# USBTypeConverter.net
KiCad netlist of a schematic drawn in EAGLE
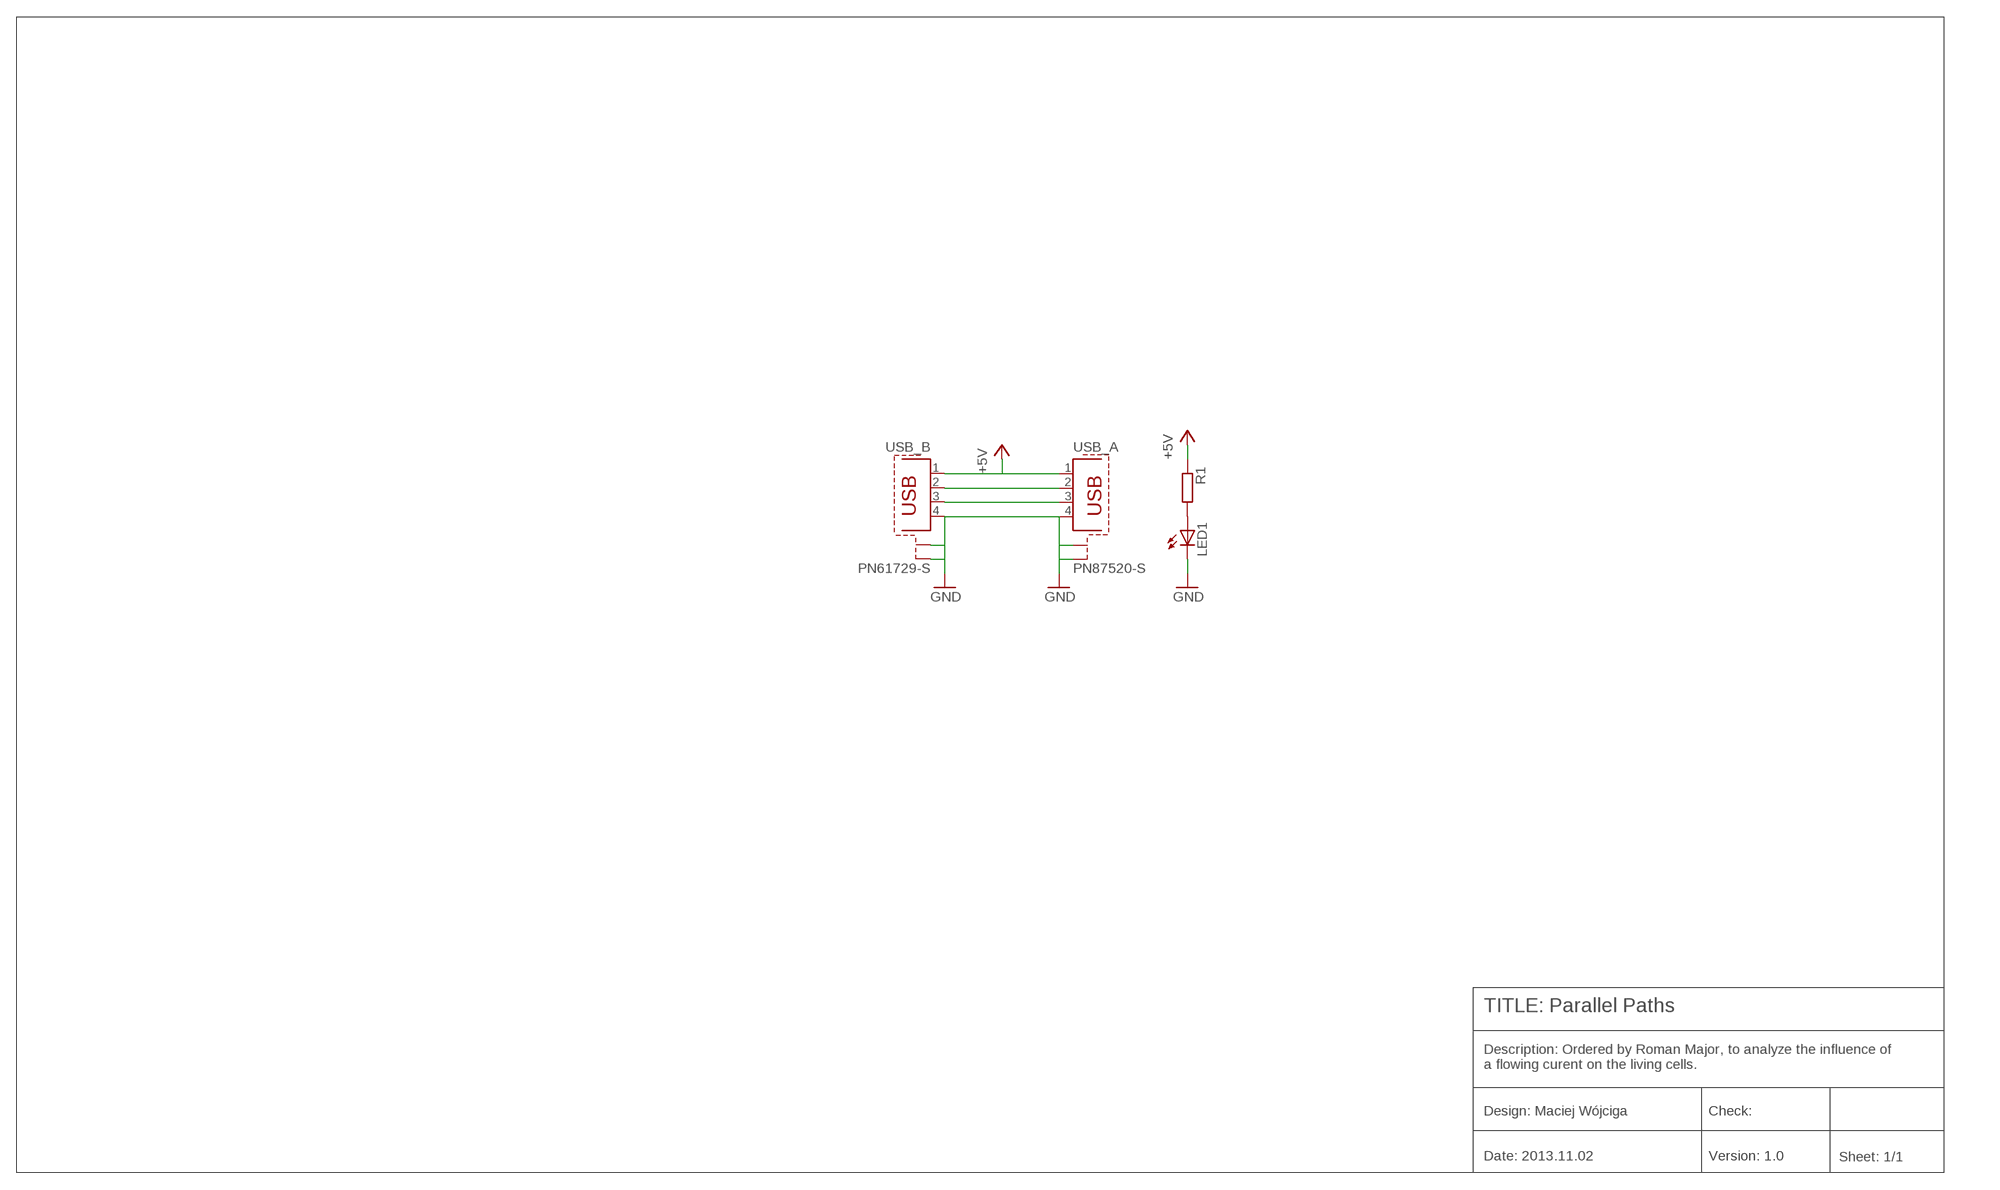
[diagram p0: schematic, sheet 1]

(export (version "E")
  (design (tool "Eeschema 10.0.6"))
  (components
    (comp (ref "LED1")
      (value "LED3MM")
      (footprint "eagle-import:LED3MM")
      (libsource (lib "eagle-import") (part "LED3MM"))
    )
    (comp (ref "R1")
      (value "R-EU_0207/10")
      (footprint "eagle-import:0207_10")
      (libsource (lib "eagle-import") (part "R-EU_0207/10"))
    )
    (comp (ref "USB_A")
      (value "PN87520-S")
      (footprint "eagle-import:PN87520-S")
      (libsource (lib "eagle-import") (part "PN87520-S"))
    )
    (comp (ref "USB_B")
      (value "PN61729-S")
      (footprint "eagle-import:PN61729-S")
      (libsource (lib "eagle-import") (part "PN61729-S"))
    )
  )
  (nets
    (net (code "1") (name "+5V") (class "Default")
      (node (ref "R1") (pin "1") (pinfunction "1_1") (pintype "passive"))
      (node (ref "USB_A") (pin "1") (pinfunction "1_1") (pintype "passive"))
      (node (ref "USB_B") (pin "1") (pinfunction "1_1") (pintype "passive"))
    )
    (net (code "2") (name "GND") (class "Default")
      (node (ref "LED1") (pin "K") (pinfunction "C_K") (pintype "passive"))
      (node (ref "USB_A") (pin "4") (pinfunction "4_4") (pintype "passive"))
      (node (ref "USB_A") (pin "S1") (pinfunction "S1_S1") (pintype "passive"))
      (node (ref "USB_A") (pin "S2") (pinfunction "S2_S2") (pintype "passive"))
      (node (ref "USB_B") (pin "4") (pinfunction "4_4") (pintype "passive"))
      (node (ref "USB_B") (pin "S1") (pinfunction "S1_S1") (pintype "passive"))
      (node (ref "USB_B") (pin "S2") (pinfunction "S2_S2") (pintype "passive"))
    )
    (net (code "3") (name "Net-(LED1-PadA)") (class "Default")
      (node (ref "LED1") (pin "A") (pinfunction "A_A") (pintype "passive"))
      (node (ref "R1") (pin "2") (pinfunction "2_2") (pintype "passive"))
    )
    (net (code "4") (name "Net-(USB_A-Pad2)") (class "Default")
      (node (ref "USB_A") (pin "2") (pinfunction "2_2") (pintype "passive"))
      (node (ref "USB_B") (pin "2") (pinfunction "2_2") (pintype "passive"))
    )
    (net (code "5") (name "Net-(USB_A-Pad3)") (class "Default")
      (node (ref "USB_A") (pin "3") (pinfunction "3_3") (pintype "passive"))
      (node (ref "USB_B") (pin "3") (pinfunction "3_3") (pintype "passive"))
    )
  )
)
